# inverted_pendulum_schematic.net
KiCad netlist of a schematic drawn in EAGLE
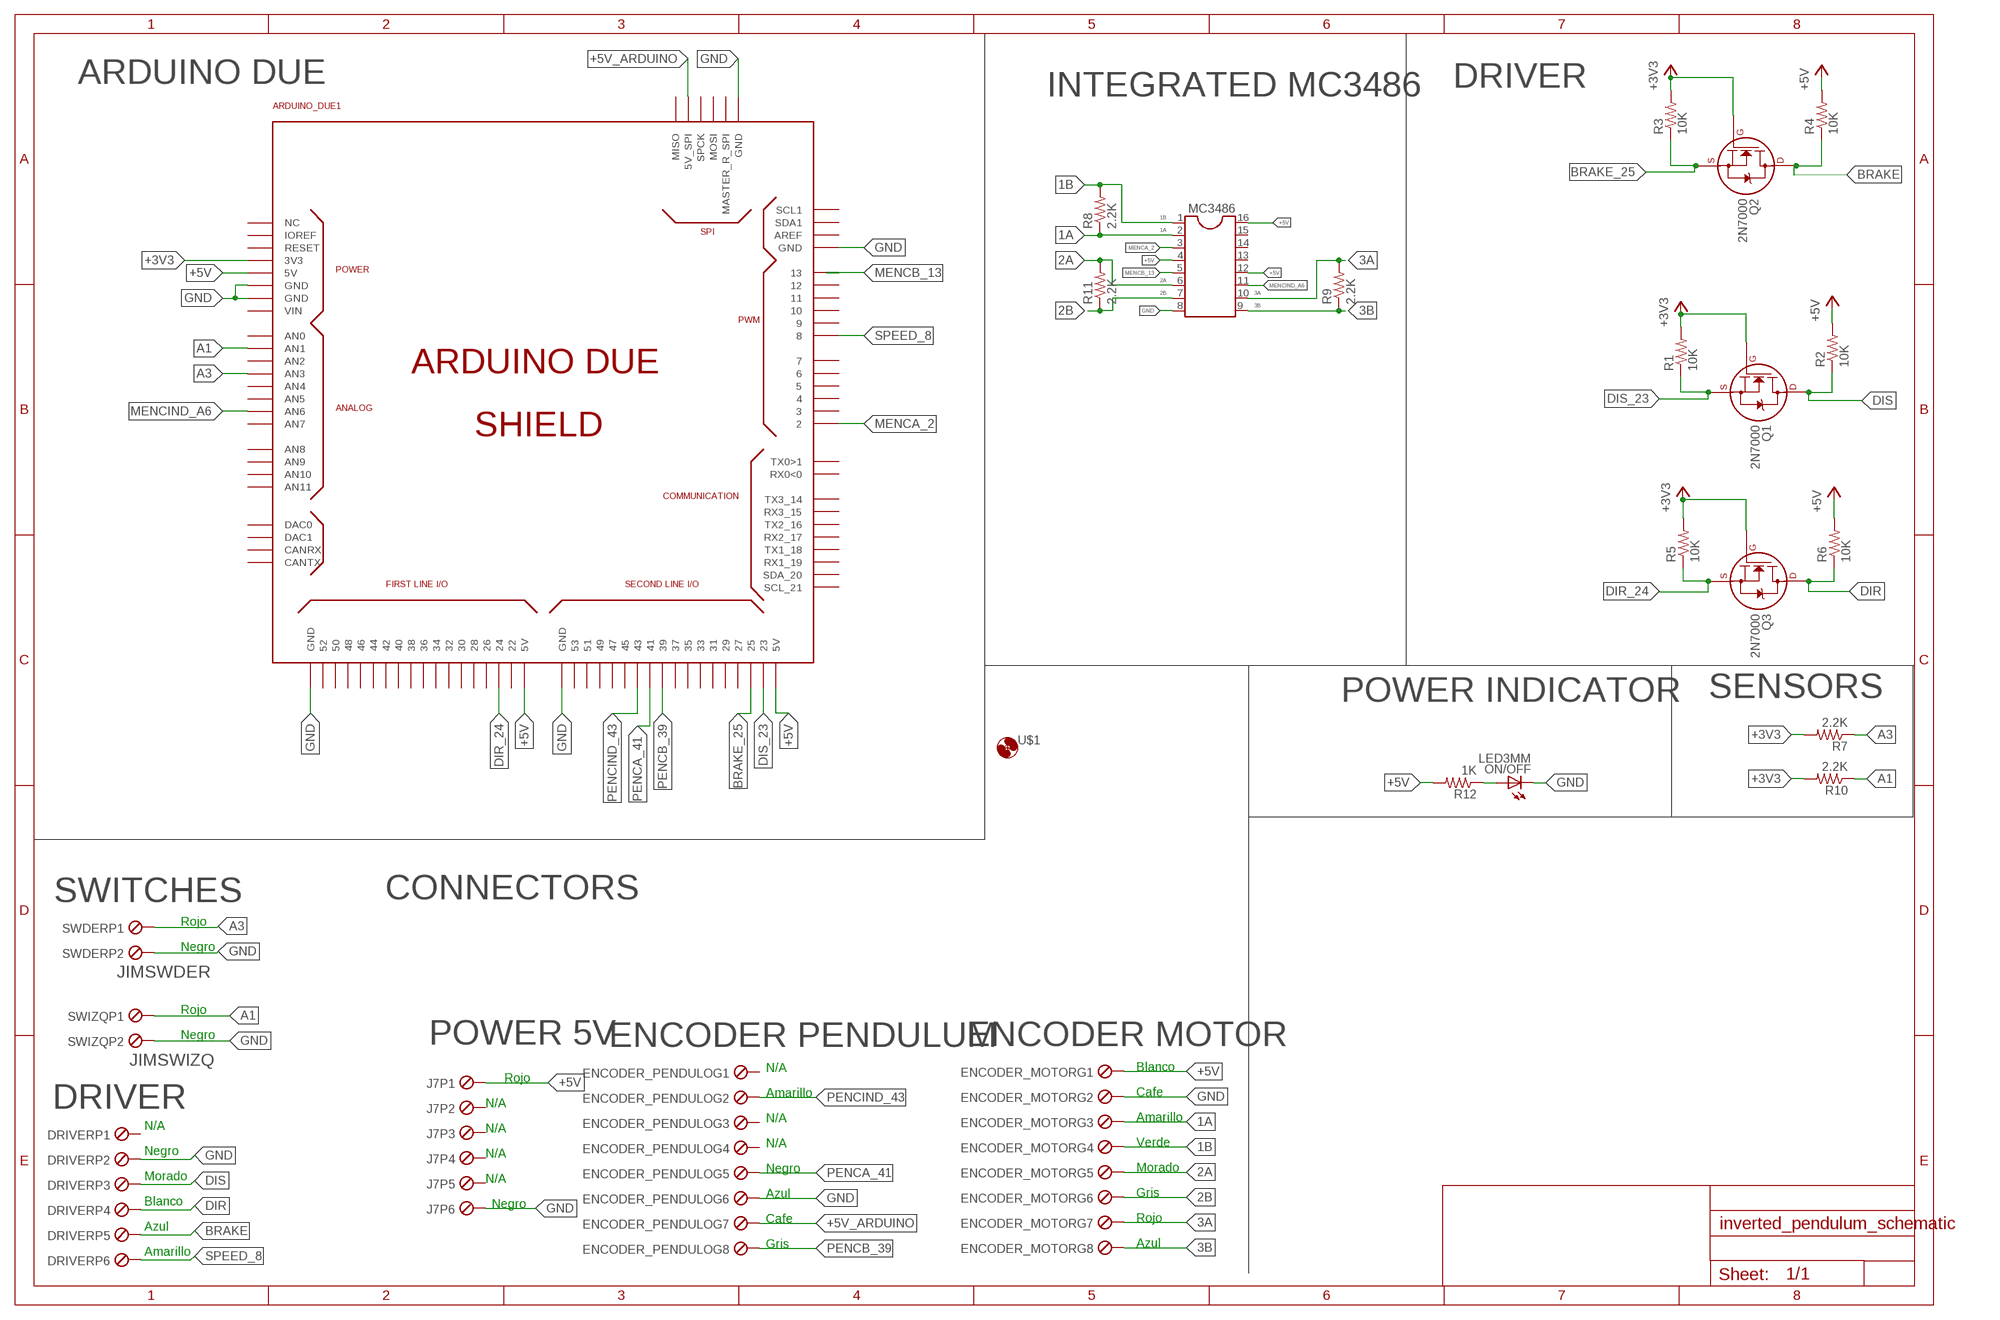
[diagram p0: schematic, sheet 1]

(export (version "E")
  (design (tool "Eeschema 10.0.6"))
  (components
    (comp (ref "ARDUINO_DUE1")
      (value "ARDUINO_DUE_SHIELD")
      (footprint "eagle-import:ARDUINO_DUE_SHIELD")
      (libsource (lib "eagle-import") (part "ARDUINO_DUE_SHIELD"))
    )
    (comp (ref "DRIVER")
      (value "PTSM1/6-2,50_TH")
      (footprint "eagle-import:6PTSMTH")
      (libsource (lib "eagle-import") (part "PTSM1/6-2,50_TH"))
    )
    (comp (ref "ENCODER_MOTOR")
      (value "PTSM1/8-2,50_TH")
      (footprint "eagle-import:8PTSMTH")
      (libsource (lib "eagle-import") (part "PTSM1/8-2,50_TH"))
    )
    (comp (ref "ENCODER_PENDULO")
      (value "PTSM1/8-2,50_TH")
      (footprint "eagle-import:8PTSMTH")
      (libsource (lib "eagle-import") (part "PTSM1/8-2,50_TH"))
    )
    (comp (ref "J7")
      (value "PTSM1/6-2,50_TH")
      (footprint "eagle-import:6PTSMTH")
      (libsource (lib "eagle-import") (part "PTSM1/6-2,50_TH"))
    )
    (comp (ref "MC3486")
      (value "DIL16S")
      (footprint "eagle-import:SOCKET-16")
      (libsource (lib "eagle-import") (part "DIL16S"))
    )
    (comp (ref "ON/OFF")
      (value "LED3MM")
      (footprint "eagle-import:LED3MM")
      (libsource (lib "eagle-import") (part "LED3MM"))
    )
    (comp (ref "Q1")
      (value "2N7000")
      (footprint "eagle-import:TO-92")
      (libsource (lib "eagle-import") (part "2N700_TO920"))
    )
    (comp (ref "Q2")
      (value "2N7000")
      (footprint "eagle-import:TO-92")
      (libsource (lib "eagle-import") (part "2N700_TO920"))
    )
    (comp (ref "Q3")
      (value "2N7000")
      (footprint "eagle-import:TO-92")
      (libsource (lib "eagle-import") (part "2N700_TO920"))
    )
    (comp (ref "R1")
      (value "10K")
      (footprint "eagle-import:0207_10")
      (libsource (lib "eagle-import") (part "R-US_0207/10"))
    )
    (comp (ref "R2")
      (value "10K")
      (footprint "eagle-import:0207_10")
      (libsource (lib "eagle-import") (part "R-US_0207/10"))
    )
    (comp (ref "R3")
      (value "10K")
      (footprint "eagle-import:0207_10")
      (libsource (lib "eagle-import") (part "R-US_0207/10"))
    )
    (comp (ref "R4")
      (value "10K")
      (footprint "eagle-import:0207_10")
      (libsource (lib "eagle-import") (part "R-US_0207/10"))
    )
    (comp (ref "R5")
      (value "10K")
      (footprint "eagle-import:0207_10")
      (libsource (lib "eagle-import") (part "R-US_0207/10"))
    )
    (comp (ref "R6")
      (value "10K")
      (footprint "eagle-import:0207_10")
      (libsource (lib "eagle-import") (part "R-US_0207/10"))
    )
    (comp (ref "R7")
      (value "2.2K")
      (footprint "eagle-import:0207_10")
      (libsource (lib "eagle-import") (part "R-US_0207/10"))
    )
    (comp (ref "R8")
      (value "2.2K")
      (footprint "eagle-import:0207_10")
      (libsource (lib "eagle-import") (part "R-US_0207/10"))
    )
    (comp (ref "R9")
      (value "2.2K")
      (footprint "eagle-import:0207_10")
      (libsource (lib "eagle-import") (part "R-US_0207/10"))
    )
    (comp (ref "R10")
      (value "2.2K")
      (footprint "eagle-import:0207_10")
      (libsource (lib "eagle-import") (part "R-US_0207/10"))
    )
    (comp (ref "R11")
      (value "2.2K")
      (footprint "eagle-import:0207_10")
      (libsource (lib "eagle-import") (part "R-US_0207/10"))
    )
    (comp (ref "R12")
      (value "1K")
      (footprint "eagle-import:0207_10")
      (libsource (lib "eagle-import") (part "R-US_0207/10"))
    )
    (comp (ref "SWDER")
      (value "PTSM1/2-2,50_TH")
      (footprint "eagle-import:2PTSMTH")
      (libsource (lib "eagle-import") (part "PTSM1/2-2,50_TH"))
    )
    (comp (ref "SWIZQ")
      (value "PTSM1/2-2,50_TH")
      (footprint "eagle-import:2PTSMTH")
      (libsource (lib "eagle-import") (part "PTSM1/2-2,50_TH"))
    )
    (comp (ref "U$1")
      (value "FIDUCIAL")
      (footprint "eagle-import:ROLAND_1")
      (libsource (lib "eagle-import") (part "FIDUCIAL"))
    )
  )
  (nets
    (net (code "1") (name "+3V3") (class "Default")
      (node (ref "ARDUINO_DUE1") (pin "3V3") (pinfunction "3V3_3V3") (pintype "bidirectional"))
      (node (ref "Q1") (pin "2") (pinfunction "G_2") (pintype "tri_state"))
      (node (ref "Q2") (pin "2") (pinfunction "G_2") (pintype "tri_state"))
      (node (ref "Q3") (pin "2") (pinfunction "G_2") (pintype "tri_state"))
      (node (ref "R1") (pin "2") (pinfunction "2_2") (pintype "passive"))
      (node (ref "R10") (pin "2") (pinfunction "2_2") (pintype "passive"))
      (node (ref "R3") (pin "2") (pinfunction "2_2") (pintype "passive"))
      (node (ref "R5") (pin "2") (pinfunction "2_2") (pintype "passive"))
      (node (ref "R7") (pin "2") (pinfunction "2_2") (pintype "passive"))
    )
    (net (code "2") (name "+5V") (class "Default")
      (node (ref "ARDUINO_DUE1") (pin "5V0") (pinfunction "5V_5V0") (pintype "bidirectional"))
      (node (ref "ARDUINO_DUE1") (pin "5V0_1") (pinfunction "5V_5V0_1") (pintype "bidirectional"))
      (node (ref "ARDUINO_DUE1") (pin "5V0_2") (pinfunction "5V_5V0_2") (pintype "bidirectional"))
      (node (ref "ENCODER_MOTOR") (pin "P$1") (pinfunction "1_P$1") (pintype "passive"))
      (node (ref "J7") (pin "P$1") (pinfunction "1_P$1") (pintype "passive"))
      (node (ref "MC3486") (pin "12") (pinfunction "12_12") (pintype "passive"))
      (node (ref "MC3486") (pin "16") (pinfunction "16_16") (pintype "passive"))
      (node (ref "MC3486") (pin "4") (pinfunction "4_4") (pintype "passive"))
      (node (ref "R12") (pin "2") (pinfunction "2_2") (pintype "passive"))
      (node (ref "R2") (pin "2") (pinfunction "2_2") (pintype "passive"))
      (node (ref "R4") (pin "2") (pinfunction "2_2") (pintype "passive"))
      (node (ref "R6") (pin "2") (pinfunction "2_2") (pintype "passive"))
    )
    (net (code "3") (name "+5V_ARDUINO") (class "Default")
      (node (ref "ARDUINO_DUE1") (pin "5V_2") (pinfunction "5V_SPI_5V_2") (pintype "bidirectional"))
      (node (ref "ENCODER_PENDULO") (pin "P$7") (pinfunction "1_P$7") (pintype "passive"))
    )
    (net (code "4") (name "1A") (class "Default")
      (node (ref "ENCODER_MOTOR") (pin "P$3") (pinfunction "1_P$3") (pintype "passive"))
      (node (ref "MC3486") (pin "2") (pinfunction "2_2") (pintype "passive"))
      (node (ref "R8") (pin "1") (pinfunction "1_1") (pintype "passive"))
    )
    (net (code "5") (name "1B") (class "Default")
      (node (ref "ENCODER_MOTOR") (pin "P$4") (pinfunction "1_P$4") (pintype "passive"))
      (node (ref "MC3486") (pin "1") (pinfunction "1_1") (pintype "passive"))
      (node (ref "R8") (pin "2") (pinfunction "2_2") (pintype "passive"))
    )
    (net (code "6") (name "2A") (class "Default")
      (node (ref "ENCODER_MOTOR") (pin "P$5") (pinfunction "1_P$5") (pintype "passive"))
      (node (ref "MC3486") (pin "6") (pinfunction "6_6") (pintype "passive"))
      (node (ref "R11") (pin "2") (pinfunction "2_2") (pintype "passive"))
    )
    (net (code "7") (name "2B") (class "Default")
      (node (ref "ENCODER_MOTOR") (pin "P$6") (pinfunction "1_P$6") (pintype "passive"))
      (node (ref "MC3486") (pin "7") (pinfunction "7_7") (pintype "passive"))
      (node (ref "R11") (pin "1") (pinfunction "1_1") (pintype "passive"))
    )
    (net (code "8") (name "3A") (class "Default")
      (node (ref "ENCODER_MOTOR") (pin "P$7") (pinfunction "1_P$7") (pintype "passive"))
      (node (ref "MC3486") (pin "10") (pinfunction "10_10") (pintype "passive"))
      (node (ref "R9") (pin "2") (pinfunction "2_2") (pintype "passive"))
    )
    (net (code "9") (name "3B") (class "Default")
      (node (ref "ENCODER_MOTOR") (pin "P$8") (pinfunction "1_P$8") (pintype "passive"))
      (node (ref "MC3486") (pin "9") (pinfunction "9_9") (pintype "passive"))
      (node (ref "R9") (pin "1") (pinfunction "1_1") (pintype "passive"))
    )
    (net (code "10") (name "A1") (class "Default")
      (node (ref "ARDUINO_DUE1") (pin "A1") (pinfunction "AN1_A1") (pintype "bidirectional"))
      (node (ref "R10") (pin "1") (pinfunction "1_1") (pintype "passive"))
      (node (ref "SWIZQ") (pin "1") (pinfunction "1_1") (pintype "passive"))
    )
    (net (code "11") (name "A3") (class "Default")
      (node (ref "ARDUINO_DUE1") (pin "A3") (pinfunction "AN3_A3") (pintype "bidirectional"))
      (node (ref "R7") (pin "1") (pinfunction "1_1") (pintype "passive"))
      (node (ref "SWDER") (pin "1") (pinfunction "1_1") (pintype "passive"))
    )
    (net (code "12") (name "BRAKE") (class "Default")
      (node (ref "DRIVER") (pin "P$5") (pinfunction "1_P$5") (pintype "passive"))
      (node (ref "Q2") (pin "3") (pinfunction "D_3") (pintype "bidirectional"))
      (node (ref "R4") (pin "1") (pinfunction "1_1") (pintype "passive"))
    )
    (net (code "13") (name "BRAKE_25") (class "Default")
      (node (ref "ARDUINO_DUE1") (pin "25") (pinfunction "25_25") (pintype "bidirectional"))
      (node (ref "Q2") (pin "1") (pinfunction "S_1") (pintype "bidirectional"))
      (node (ref "R3") (pin "1") (pinfunction "1_1") (pintype "passive"))
    )
    (net (code "14") (name "DIR") (class "Default")
      (node (ref "DRIVER") (pin "P$4") (pinfunction "1_P$4") (pintype "passive"))
      (node (ref "Q3") (pin "3") (pinfunction "D_3") (pintype "bidirectional"))
      (node (ref "R6") (pin "1") (pinfunction "1_1") (pintype "passive"))
    )
    (net (code "15") (name "DIR_24") (class "Default")
      (node (ref "ARDUINO_DUE1") (pin "24") (pinfunction "24_24") (pintype "bidirectional"))
      (node (ref "Q3") (pin "1") (pinfunction "S_1") (pintype "bidirectional"))
      (node (ref "R5") (pin "1") (pinfunction "1_1") (pintype "passive"))
    )
    (net (code "16") (name "DIS") (class "Default")
      (node (ref "DRIVER") (pin "P$3") (pinfunction "1_P$3") (pintype "passive"))
      (node (ref "Q1") (pin "3") (pinfunction "D_3") (pintype "bidirectional"))
      (node (ref "R2") (pin "1") (pinfunction "1_1") (pintype "passive"))
    )
    (net (code "17") (name "DIS_23") (class "Default")
      (node (ref "ARDUINO_DUE1") (pin "23") (pinfunction "23_23") (pintype "bidirectional"))
      (node (ref "Q1") (pin "1") (pinfunction "S_1") (pintype "bidirectional"))
      (node (ref "R1") (pin "1") (pinfunction "1_1") (pintype "passive"))
    )
    (net (code "18") (name "GND") (class "Default")
      (node (ref "ARDUINO_DUE1") (pin "GND") (pinfunction "GND_GND") (pintype "bidirectional"))
      (node (ref "ARDUINO_DUE1") (pin "GND_1") (pinfunction "GND_GND_1") (pintype "bidirectional"))
      (node (ref "ARDUINO_DUE1") (pin "GND_2") (pinfunction "GND_GND_2") (pintype "bidirectional"))
      (node (ref "ARDUINO_DUE1") (pin "GND_3") (pinfunction "GND_GND_3") (pintype "bidirectional"))
      (node (ref "ARDUINO_DUE1") (pin "GND_4") (pinfunction "GND_GND_4") (pintype "bidirectional"))
      (node (ref "ARDUINO_DUE1") (pin "GND_5") (pinfunction "GND_GND_5") (pintype "bidirectional"))
      (node (ref "DRIVER") (pin "P$2") (pinfunction "1_P$2") (pintype "passive"))
      (node (ref "ENCODER_MOTOR") (pin "P$2") (pinfunction "1_P$2") (pintype "passive"))
      (node (ref "ENCODER_PENDULO") (pin "P$6") (pinfunction "1_P$6") (pintype "passive"))
      (node (ref "J7") (pin "P$6") (pinfunction "1_P$6") (pintype "passive"))
      (node (ref "MC3486") (pin "8") (pinfunction "8_8") (pintype "passive"))
      (node (ref "ON/OFF") (pin "K") (pinfunction "C_K") (pintype "passive"))
      (node (ref "SWDER") (pin "2") (pinfunction "1_2") (pintype "passive"))
      (node (ref "SWIZQ") (pin "2") (pinfunction "1_2") (pintype "passive"))
    )
    (net (code "19") (name "MENCA_2") (class "Default")
      (node (ref "ARDUINO_DUE1") (pin "2") (pinfunction "2_2") (pintype "bidirectional"))
      (node (ref "MC3486") (pin "3") (pinfunction "3_3") (pintype "passive"))
    )
    (net (code "20") (name "MENCB_13") (class "Default")
      (node (ref "ARDUINO_DUE1") (pin "13") (pinfunction "13_13") (pintype "bidirectional"))
      (node (ref "MC3486") (pin "5") (pinfunction "5_5") (pintype "passive"))
    )
    (net (code "21") (name "MENCIND_A6") (class "Default")
      (node (ref "ARDUINO_DUE1") (pin "A6") (pinfunction "AN6_A6") (pintype "bidirectional"))
      (node (ref "MC3486") (pin "11") (pinfunction "11_11") (pintype "passive"))
    )
    (net (code "22") (name "Net-(ON/OFF-PadA)") (class "Default")
      (node (ref "ON/OFF") (pin "A") (pinfunction "A_A") (pintype "passive"))
      (node (ref "R12") (pin "1") (pinfunction "1_1") (pintype "passive"))
    )
    (net (code "23") (name "PENCA_41") (class "Default")
      (node (ref "ARDUINO_DUE1") (pin "41") (pinfunction "41_41") (pintype "bidirectional"))
      (node (ref "ENCODER_PENDULO") (pin "P$5") (pinfunction "1_P$5") (pintype "passive"))
    )
    (net (code "24") (name "PENCB_39") (class "Default")
      (node (ref "ARDUINO_DUE1") (pin "39") (pinfunction "39_39") (pintype "bidirectional"))
      (node (ref "ENCODER_PENDULO") (pin "P$8") (pinfunction "1_P$8") (pintype "passive"))
    )
    (net (code "25") (name "PENCIND_43") (class "Default")
      (node (ref "ARDUINO_DUE1") (pin "43") (pinfunction "43_43") (pintype "bidirectional"))
      (node (ref "ENCODER_PENDULO") (pin "P$2") (pinfunction "1_P$2") (pintype "passive"))
    )
    (net (code "26") (name "SPEED_8") (class "Default")
      (node (ref "ARDUINO_DUE1") (pin "8") (pinfunction "8_8") (pintype "bidirectional"))
      (node (ref "DRIVER") (pin "P$6") (pinfunction "1_P$6") (pintype "passive"))
    )
    (net (code "27") (name "unconnected-(ARDUINO_DUE1-AN0-PadA0)") (class "Default")
      (node (ref "ARDUINO_DUE1") (pin "A0") (pinfunction "AN0_A0") (pintype "bidirectional"))
    )
    (net (code "28") (name "unconnected-(ARDUINO_DUE1-AN2-PadA2)") (class "Default")
      (node (ref "ARDUINO_DUE1") (pin "A2") (pinfunction "AN2_A2") (pintype "bidirectional"))
    )
    (net (code "29") (name "unconnected-(ARDUINO_DUE1-AN4-PadA4)") (class "Default")
      (node (ref "ARDUINO_DUE1") (pin "A4") (pinfunction "AN4_A4") (pintype "bidirectional"))
    )
    (net (code "30") (name "unconnected-(ARDUINO_DUE1-AN5-PadA5)") (class "Default")
      (node (ref "ARDUINO_DUE1") (pin "A5") (pinfunction "AN5_A5") (pintype "bidirectional"))
    )
    (net (code "31") (name "unconnected-(ARDUINO_DUE1-AN7-PadA7)") (class "Default")
      (node (ref "ARDUINO_DUE1") (pin "A7") (pinfunction "AN7_A7") (pintype "bidirectional"))
    )
    (net (code "32") (name "unconnected-(ARDUINO_DUE1-AN8-PadA8)") (class "Default")
      (node (ref "ARDUINO_DUE1") (pin "A8") (pinfunction "AN8_A8") (pintype "bidirectional"))
    )
    (net (code "33") (name "unconnected-(ARDUINO_DUE1-AN9-PadA9)") (class "Default")
      (node (ref "ARDUINO_DUE1") (pin "A9") (pinfunction "AN9_A9") (pintype "bidirectional"))
    )
    (net (code "34") (name "unconnected-(ARDUINO_DUE1-AN10-PadA10)") (class "Default")
      (node (ref "ARDUINO_DUE1") (pin "A10") (pinfunction "AN10_A10") (pintype "bidirectional"))
    )
    (net (code "35") (name "unconnected-(ARDUINO_DUE1-AN11-PadA11)") (class "Default")
      (node (ref "ARDUINO_DUE1") (pin "A11") (pinfunction "AN11_A11") (pintype "bidirectional"))
    )
    (net (code "36") (name "unconnected-(ARDUINO_DUE1-MASTER_R_SPI-PadMASTER_RESET_SPI)") (class "Default")
      (node (ref "ARDUINO_DUE1") (pin "MASTER_RESET_SPI") (pinfunction "MASTER_R_SPI_MASTER_RESET_SPI") (pintype "bidirectional"))
    )
    (net (code "37") (name "unconnected-(ARDUINO_DUE1-NC-PadNC_2)") (class "Default")
      (node (ref "ARDUINO_DUE1") (pin "NC_2") (pinfunction "NC_NC_2") (pintype "no_connect"))
    )
    (net (code "38") (name "unconnected-(ARDUINO_DUE1-Pad3)") (class "Default")
      (node (ref "ARDUINO_DUE1") (pin "3") (pinfunction "3_3") (pintype "bidirectional"))
    )
    (net (code "39") (name "unconnected-(ARDUINO_DUE1-Pad4)") (class "Default")
      (node (ref "ARDUINO_DUE1") (pin "4") (pinfunction "4_4") (pintype "bidirectional"))
    )
    (net (code "40") (name "unconnected-(ARDUINO_DUE1-Pad5)") (class "Default")
      (node (ref "ARDUINO_DUE1") (pin "5") (pinfunction "5_5") (pintype "bidirectional"))
    )
    (net (code "41") (name "unconnected-(ARDUINO_DUE1-Pad6)") (class "Default")
      (node (ref "ARDUINO_DUE1") (pin "6") (pinfunction "6_6") (pintype "bidirectional"))
    )
    (net (code "42") (name "unconnected-(ARDUINO_DUE1-Pad7)") (class "Default")
      (node (ref "ARDUINO_DUE1") (pin "7") (pinfunction "7_7") (pintype "bidirectional"))
    )
    (net (code "43") (name "unconnected-(ARDUINO_DUE1-Pad9)") (class "Default")
      (node (ref "ARDUINO_DUE1") (pin "9") (pinfunction "9_9") (pintype "bidirectional"))
    )
    (net (code "44") (name "unconnected-(ARDUINO_DUE1-Pad10)") (class "Default")
      (node (ref "ARDUINO_DUE1") (pin "10") (pinfunction "10_10") (pintype "bidirectional"))
    )
    (net (code "45") (name "unconnected-(ARDUINO_DUE1-Pad11)") (class "Default")
      (node (ref "ARDUINO_DUE1") (pin "11") (pinfunction "11_11") (pintype "bidirectional"))
    )
    (net (code "46") (name "unconnected-(ARDUINO_DUE1-Pad12)") (class "Default")
      (node (ref "ARDUINO_DUE1") (pin "12") (pinfunction "12_12") (pintype "bidirectional"))
    )
    (net (code "47") (name "unconnected-(ARDUINO_DUE1-Pad22)") (class "Default")
      (node (ref "ARDUINO_DUE1") (pin "22") (pinfunction "22_22") (pintype "bidirectional"))
    )
    (net (code "48") (name "unconnected-(ARDUINO_DUE1-Pad26)") (class "Default")
      (node (ref "ARDUINO_DUE1") (pin "26") (pinfunction "26_26") (pintype "bidirectional"))
    )
    (net (code "49") (name "unconnected-(ARDUINO_DUE1-Pad27)") (class "Default")
      (node (ref "ARDUINO_DUE1") (pin "27") (pinfunction "27_27") (pintype "bidirectional"))
    )
    (net (code "50") (name "unconnected-(ARDUINO_DUE1-Pad28)") (class "Default")
      (node (ref "ARDUINO_DUE1") (pin "28") (pinfunction "28_28") (pintype "bidirectional"))
    )
    (net (code "51") (name "unconnected-(ARDUINO_DUE1-Pad29)") (class "Default")
      (node (ref "ARDUINO_DUE1") (pin "29") (pinfunction "29_29") (pintype "bidirectional"))
    )
    (net (code "52") (name "unconnected-(ARDUINO_DUE1-Pad30)") (class "Default")
      (node (ref "ARDUINO_DUE1") (pin "30") (pinfunction "30_30") (pintype "bidirectional"))
    )
    (net (code "53") (name "unconnected-(ARDUINO_DUE1-Pad31)") (class "Default")
      (node (ref "ARDUINO_DUE1") (pin "31") (pinfunction "31_31") (pintype "bidirectional"))
    )
    (net (code "54") (name "unconnected-(ARDUINO_DUE1-Pad32)") (class "Default")
      (node (ref "ARDUINO_DUE1") (pin "32") (pinfunction "32_32") (pintype "bidirectional"))
    )
    (net (code "55") (name "unconnected-(ARDUINO_DUE1-Pad33)") (class "Default")
      (node (ref "ARDUINO_DUE1") (pin "33") (pinfunction "33_33") (pintype "bidirectional"))
    )
    (net (code "56") (name "unconnected-(ARDUINO_DUE1-Pad34)") (class "Default")
      (node (ref "ARDUINO_DUE1") (pin "34") (pinfunction "34_34") (pintype "bidirectional"))
    )
    (net (code "57") (name "unconnected-(ARDUINO_DUE1-Pad35)") (class "Default")
      (node (ref "ARDUINO_DUE1") (pin "35") (pinfunction "35_35") (pintype "bidirectional"))
    )
    (net (code "58") (name "unconnected-(ARDUINO_DUE1-Pad36)") (class "Default")
      (node (ref "ARDUINO_DUE1") (pin "36") (pinfunction "36_36") (pintype "bidirectional"))
    )
    (net (code "59") (name "unconnected-(ARDUINO_DUE1-Pad37)") (class "Default")
      (node (ref "ARDUINO_DUE1") (pin "37") (pinfunction "37_37") (pintype "bidirectional"))
    )
    (net (code "60") (name "unconnected-(ARDUINO_DUE1-Pad38)") (class "Default")
      (node (ref "ARDUINO_DUE1") (pin "38") (pinfunction "38_38") (pintype "bidirectional"))
    )
    (net (code "61") (name "unconnected-(ARDUINO_DUE1-Pad40)") (class "Default")
      (node (ref "ARDUINO_DUE1") (pin "40") (pinfunction "40_40") (pintype "bidirectional"))
    )
    (net (code "62") (name "unconnected-(ARDUINO_DUE1-Pad42)") (class "Default")
      (node (ref "ARDUINO_DUE1") (pin "42") (pinfunction "42_42") (pintype "bidirectional"))
    )
    (net (code "63") (name "unconnected-(ARDUINO_DUE1-Pad44)") (class "Default")
      (node (ref "ARDUINO_DUE1") (pin "44") (pinfunction "44_44") (pintype "bidirectional"))
    )
    (net (code "64") (name "unconnected-(ARDUINO_DUE1-Pad45)") (class "Default")
      (node (ref "ARDUINO_DUE1") (pin "45") (pinfunction "45_45") (pintype "bidirectional"))
    )
    (net (code "65") (name "unconnected-(ARDUINO_DUE1-Pad46)") (class "Default")
      (node (ref "ARDUINO_DUE1") (pin "46") (pinfunction "46_46") (pintype "bidirectional"))
    )
    (net (code "66") (name "unconnected-(ARDUINO_DUE1-Pad47)") (class "Default")
      (node (ref "ARDUINO_DUE1") (pin "47") (pinfunction "47_47") (pintype "bidirectional"))
    )
    (net (code "67") (name "unconnected-(ARDUINO_DUE1-Pad48)") (class "Default")
      (node (ref "ARDUINO_DUE1") (pin "48") (pinfunction "48_48") (pintype "bidirectional"))
    )
    (net (code "68") (name "unconnected-(ARDUINO_DUE1-Pad49)") (class "Default")
      (node (ref "ARDUINO_DUE1") (pin "49") (pinfunction "49_49") (pintype "bidirectional"))
    )
    (net (code "69") (name "unconnected-(ARDUINO_DUE1-Pad50)") (class "Default")
      (node (ref "ARDUINO_DUE1") (pin "50") (pinfunction "50_50") (pintype "bidirectional"))
    )
    (net (code "70") (name "unconnected-(ARDUINO_DUE1-Pad51)") (class "Default")
      (node (ref "ARDUINO_DUE1") (pin "51") (pinfunction "51_51") (pintype "bidirectional"))
    )
    (net (code "71") (name "unconnected-(ARDUINO_DUE1-Pad52)") (class "Default")
      (node (ref "ARDUINO_DUE1") (pin "52") (pinfunction "52_52") (pintype "bidirectional"))
    )
    (net (code "72") (name "unconnected-(ARDUINO_DUE1-Pad53)") (class "Default")
      (node (ref "ARDUINO_DUE1") (pin "53") (pinfunction "53_53") (pintype "bidirectional"))
    )
    (net (code "73") (name "unconnected-(ARDUINO_DUE1-PadAREF)") (class "Default")
      (node (ref "ARDUINO_DUE1") (pin "AREF") (pinfunction "AREF_AREF") (pintype "bidirectional"))
    )
    (net (code "74") (name "unconnected-(ARDUINO_DUE1-PadCANRX)") (class "Default")
      (node (ref "ARDUINO_DUE1") (pin "CANRX") (pinfunction "CANRX_CANRX") (pintype "bidirectional"))
    )
    (net (code "75") (name "unconnected-(ARDUINO_DUE1-PadCANTX)") (class "Default")
      (node (ref "ARDUINO_DUE1") (pin "CANTX") (pinfunction "CANTX_CANTX") (pintype "bidirectional"))
    )
    (net (code "76") (name "unconnected-(ARDUINO_DUE1-PadDAC0)") (class "Default")
      (node (ref "ARDUINO_DUE1") (pin "DAC0") (pinfunction "DAC0_DAC0") (pintype "bidirectional"))
    )
    (net (code "77") (name "unconnected-(ARDUINO_DUE1-PadDAC1)") (class "Default")
      (node (ref "ARDUINO_DUE1") (pin "DAC1") (pinfunction "DAC1_DAC1") (pintype "bidirectional"))
    )
    (net (code "78") (name "unconnected-(ARDUINO_DUE1-PadIOREF)") (class "Default")
      (node (ref "ARDUINO_DUE1") (pin "IOREF") (pinfunction "IOREF_IOREF") (pintype "bidirectional"))
    )
    (net (code "79") (name "unconnected-(ARDUINO_DUE1-PadMISO)") (class "Default")
      (node (ref "ARDUINO_DUE1") (pin "MISO") (pinfunction "MISO_MISO") (pintype "bidirectional"))
    )
    (net (code "80") (name "unconnected-(ARDUINO_DUE1-PadMOSI)") (class "Default")
      (node (ref "ARDUINO_DUE1") (pin "MOSI") (pinfunction "MOSI_MOSI") (pintype "bidirectional"))
    )
    (net (code "81") (name "unconnected-(ARDUINO_DUE1-PadRESET)") (class "Default")
      (node (ref "ARDUINO_DUE1") (pin "RESET") (pinfunction "RESET_RESET") (pintype "bidirectional"))
    )
    (net (code "82") (name "unconnected-(ARDUINO_DUE1-PadSCL1)") (class "Default")
      (node (ref "ARDUINO_DUE1") (pin "SCL1") (pinfunction "SCL1_SCL1") (pintype "bidirectional"))
    )
    (net (code "83") (name "unconnected-(ARDUINO_DUE1-PadSDA1)") (class "Default")
      (node (ref "ARDUINO_DUE1") (pin "SDA1") (pinfunction "SDA1_SDA1") (pintype "bidirectional"))
    )
    (net (code "84") (name "unconnected-(ARDUINO_DUE1-PadSPCK)") (class "Default")
      (node (ref "ARDUINO_DUE1") (pin "SPCK") (pinfunction "SPCK_SPCK") (pintype "bidirectional"))
    )
    (net (code "85") (name "unconnected-(ARDUINO_DUE1-PadVIN)") (class "Default")
      (node (ref "ARDUINO_DUE1") (pin "VIN") (pinfunction "VIN_VIN") (pintype "bidirectional"))
    )
    (net (code "86") (name "unconnected-(ARDUINO_DUE1-RX0<0-Pad0)") (class "Default")
      (node (ref "ARDUINO_DUE1") (pin "0") (pinfunction "RX0<0_0") (pintype "bidirectional"))
    )
    (net (code "87") (name "unconnected-(ARDUINO_DUE1-RX1_19-Pad19)") (class "Default")
      (node (ref "ARDUINO_DUE1") (pin "19") (pinfunction "RX1_19_19") (pintype "bidirectional"))
    )
    (net (code "88") (name "unconnected-(ARDUINO_DUE1-RX2_17-Pad17)") (class "Default")
      (node (ref "ARDUINO_DUE1") (pin "17") (pinfunction "RX2_17_17") (pintype "bidirectional"))
    )
    (net (code "89") (name "unconnected-(ARDUINO_DUE1-RX3_15-Pad15)") (class "Default")
      (node (ref "ARDUINO_DUE1") (pin "15") (pinfunction "RX3_15_15") (pintype "bidirectional"))
    )
    (net (code "90") (name "unconnected-(ARDUINO_DUE1-SCL_21-Pad21)") (class "Default")
      (node (ref "ARDUINO_DUE1") (pin "21") (pinfunction "SCL_21_21") (pintype "bidirectional"))
    )
    (net (code "91") (name "unconnected-(ARDUINO_DUE1-SDA_20-Pad20)") (class "Default")
      (node (ref "ARDUINO_DUE1") (pin "20") (pinfunction "SDA_20_20") (pintype "bidirectional"))
    )
    (net (code "92") (name "unconnected-(ARDUINO_DUE1-TX0>1-Pad1)") (class "Default")
      (node (ref "ARDUINO_DUE1") (pin "1") (pinfunction "TX0>1_1") (pintype "bidirectional"))
    )
    (net (code "93") (name "unconnected-(ARDUINO_DUE1-TX1_18-Pad18)") (class "Default")
      (node (ref "ARDUINO_DUE1") (pin "18") (pinfunction "TX1_18_18") (pintype "bidirectional"))
    )
    (net (code "94") (name "unconnected-(ARDUINO_DUE1-TX2_16-Pad16)") (class "Default")
      (node (ref "ARDUINO_DUE1") (pin "16") (pinfunction "TX2_16_16") (pintype "bidirectional"))
    )
    (net (code "95") (name "unconnected-(ARDUINO_DUE1-TX3_14-Pad14)") (class "Default")
      (node (ref "ARDUINO_DUE1") (pin "14") (pinfunction "TX3_14_14") (pintype "bidirectional"))
    )
    (net (code "96") (name "unconnected-(DRIVERA-1-PadP$1)") (class "Default")
      (node (ref "DRIVER") (pin "P$1") (pinfunction "1_P$1") (pintype "passive"))
    )
    (net (code "97") (name "unconnected-(ENCODER_PENDULOA-1-PadP$1)") (class "Default")
      (node (ref "ENCODER_PENDULO") (pin "P$1") (pinfunction "1_P$1") (pintype "passive"))
    )
    (net (code "98") (name "unconnected-(ENCODER_PENDULOC-1-PadP$3)") (class "Default")
      (node (ref "ENCODER_PENDULO") (pin "P$3") (pinfunction "1_P$3") (pintype "passive"))
    )
    (net (code "99") (name "unconnected-(ENCODER_PENDULOD-1-PadP$4)") (class "Default")
      (node (ref "ENCODER_PENDULO") (pin "P$4") (pinfunction "1_P$4") (pintype "passive"))
    )
    (net (code "100") (name "unconnected-(J7B-1-PadP$2)") (class "Default")
      (node (ref "J7") (pin "P$2") (pinfunction "1_P$2") (pintype "passive"))
    )
    (net (code "101") (name "unconnected-(J7C-1-PadP$3)") (class "Default")
      (node (ref "J7") (pin "P$3") (pinfunction "1_P$3") (pintype "passive"))
    )
    (net (code "102") (name "unconnected-(J7D-1-PadP$4)") (class "Default")
      (node (ref "J7") (pin "P$4") (pinfunction "1_P$4") (pintype "passive"))
    )
    (net (code "103") (name "unconnected-(J7E-1-PadP$5)") (class "Default")
      (node (ref "J7") (pin "P$5") (pinfunction "1_P$5") (pintype "passive"))
    )
    (net (code "104") (name "unconnected-(MC3486-Pad13)") (class "Default")
      (node (ref "MC3486") (pin "13") (pinfunction "13_13") (pintype "passive"))
    )
    (net (code "105") (name "unconnected-(MC3486-Pad14)") (class "Default")
      (node (ref "MC3486") (pin "14") (pinfunction "14_14") (pintype "passive"))
    )
    (net (code "106") (name "unconnected-(MC3486-Pad15)") (class "Default")
      (node (ref "MC3486") (pin "15") (pinfunction "15_15") (pintype "passive"))
    )
  )
)
